# NinjaPool-1J-171004.net
KiCad netlist of a schematic drawn in EAGLE
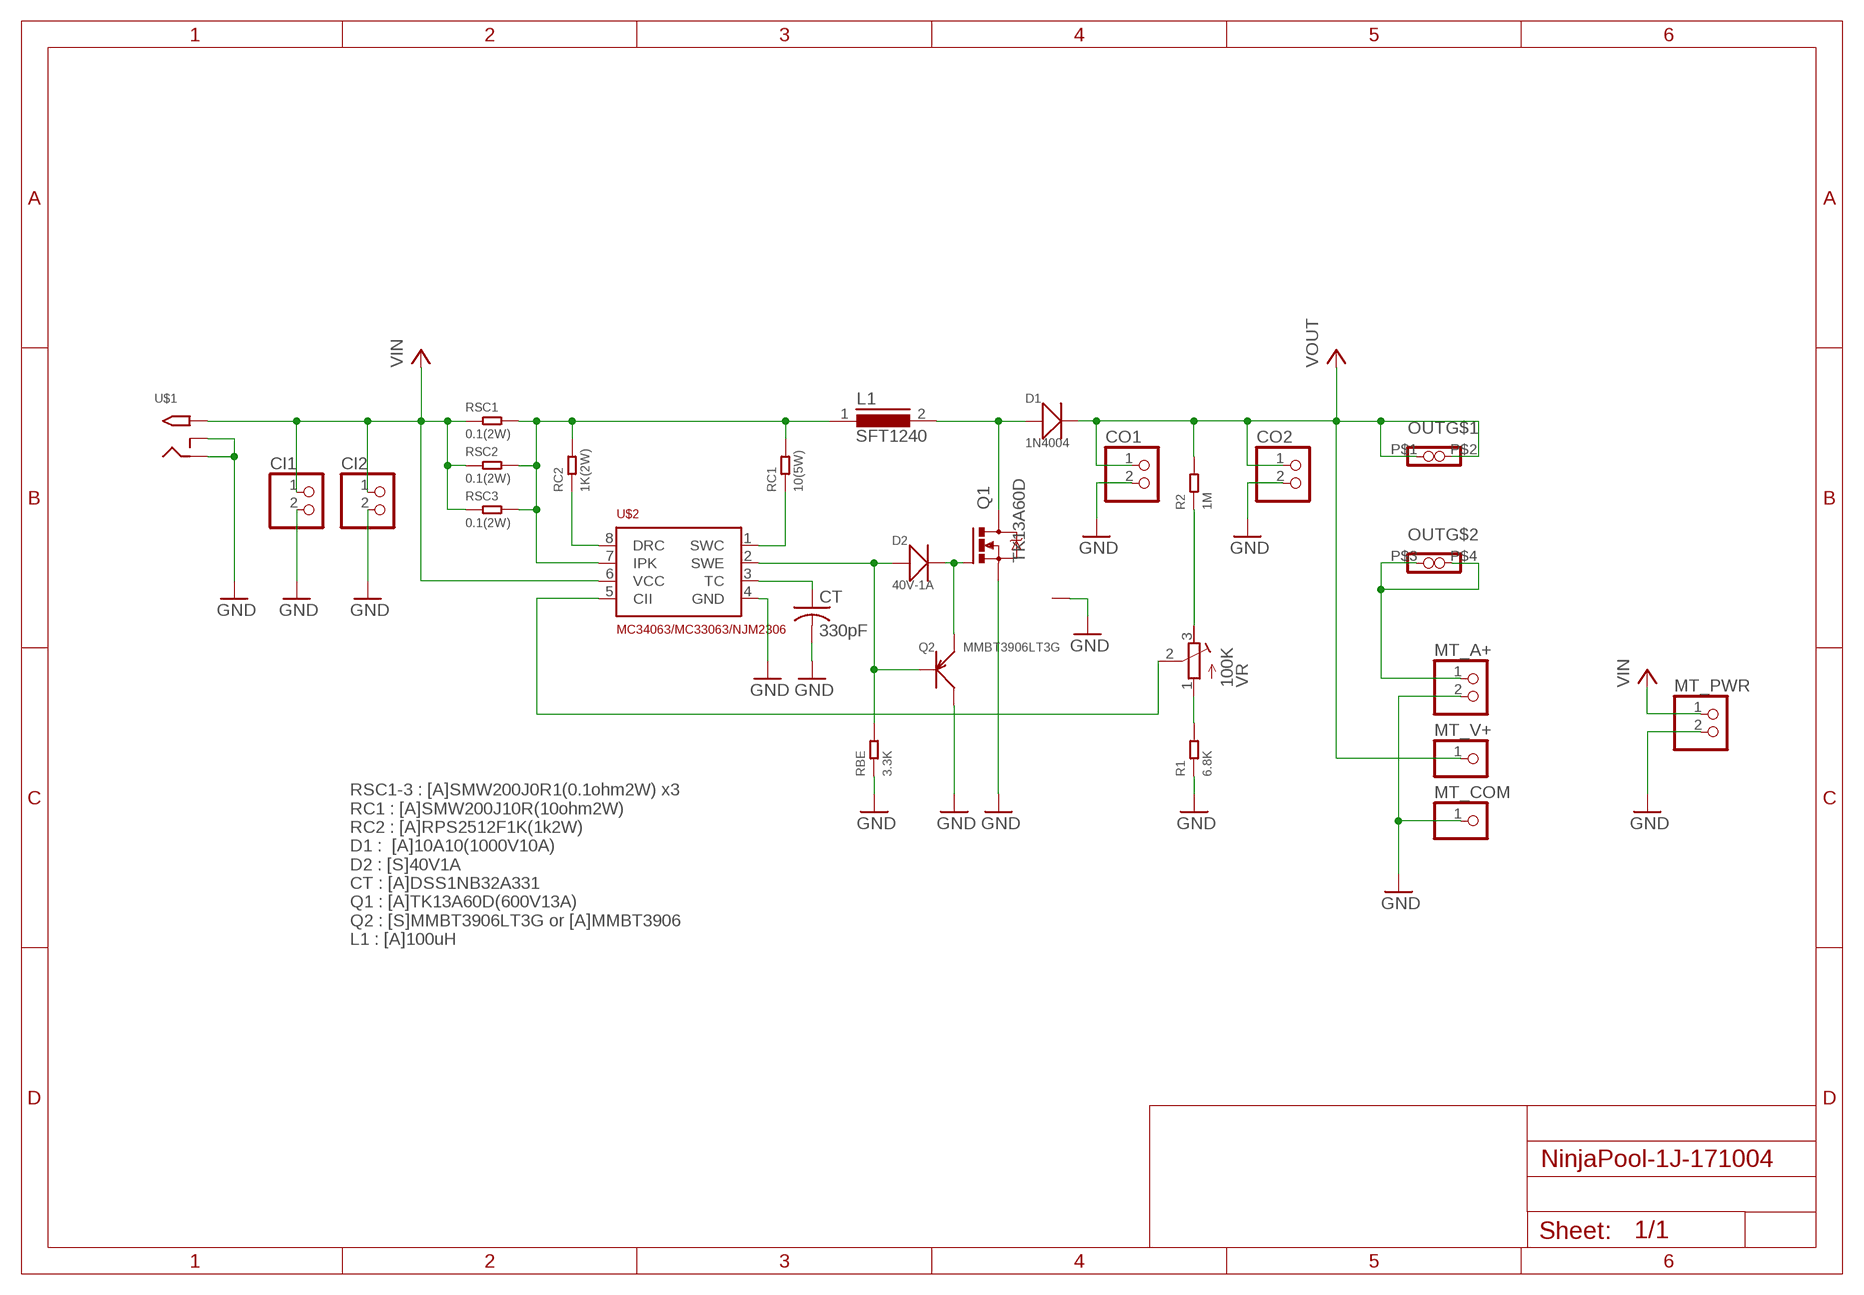
[diagram p0: schematic, sheet 1]

(export (version "E")
  (design (tool "Eeschema 10.0.6"))
  (components
    (comp (ref "CI1")
      (value "PINHD-1X2")
      (footprint "eagle-import:1X02")
      (libsource (lib "eagle-import") (part "PINHD-1X2"))
    )
    (comp (ref "CI2")
      (value "PINHD-1X2")
      (footprint "eagle-import:1X02")
      (libsource (lib "eagle-import") (part "PINHD-1X2"))
    )
    (comp (ref "CO1")
      (value "PINHD-1X2")
      (footprint "eagle-import:1X02")
      (libsource (lib "eagle-import") (part "PINHD-1X2"))
    )
    (comp (ref "CO2")
      (value "PINHD-1X2")
      (footprint "eagle-import:1X02")
      (libsource (lib "eagle-import") (part "PINHD-1X2"))
    )
    (comp (ref "CT")
      (value "330pF")
      (footprint "eagle-import:C050-024X044")
      (libsource (lib "eagle-import") (part "C-US050-024X044"))
    )
    (comp (ref "D1")
      (value "1N4004")
      (footprint "eagle-import:DO-41")
      (libsource (lib "eagle-import") (part "DIP-DIODE-400V-1A(DO-41)"))
    )
    (comp (ref "D2")
      (value "40V-1A")
      (footprint "eagle-import:DO-214AC")
      (fields (field (name "MPN") "1N5819"))
      (libsource (lib "eagle-import") (part "SMD-DIODE-SCHOTTKY-40V-1A(DO-214AC)"))
    )
    (comp (ref "HEAT")
      (value "HEAT111PB015")
      (footprint "eagle-import:HEAT11PB015")
      (libsource (lib "eagle-import") (part "HEAT111PB015"))
    )
    (comp (ref "L1")
      (value "SFT1240")
      (footprint "eagle-import:SFT1240")
      (libsource (lib "eagle-import") (part "SFT1240"))
    )
    (comp (ref "MT_A+")
      (value "PINHD-1X2")
      (footprint "eagle-import:1X02")
      (libsource (lib "eagle-import") (part "PINHD-1X2"))
    )
    (comp (ref "MT_COM")
      (value "PINHD-1X1")
      (footprint "eagle-import:1X01")
      (libsource (lib "eagle-import") (part "PINHD-1X1"))
    )
    (comp (ref "MT_PWR")
      (value "PINHD-1X2")
      (footprint "eagle-import:1X02")
      (libsource (lib "eagle-import") (part "PINHD-1X2"))
    )
    (comp (ref "MT_V+")
      (value "PINHD-1X1")
      (footprint "eagle-import:1X01")
      (libsource (lib "eagle-import") (part "PINHD-1X1"))
    )
    (comp (ref "OUT")
      (value "BANANA")
      (footprint "eagle-import:BANANA_TMP")
      (libsource (lib "eagle-import") (part "BANANA"))
    )
    (comp (ref "Q1")
      (value "TK13A60D")
      (footprint "eagle-import:TO220BV")
      (libsource (lib "eagle-import") (part "IRF520"))
    )
    (comp (ref "Q2")
      (value "MMBT3906LT3G")
      (footprint "eagle-import:SOT-23")
      (libsource (lib "eagle-import") (part "SMD-TRANSISTORS-PNP-40V-200MA-MMBT3906LT3G(SOT-23)"))
    )
    (comp (ref "R1")
      (value "6.8K")
      (footprint "eagle-import:R0603")
      (fields (field (name "MPN") "RC0805JR-07220KL"))
      (libsource (lib "eagle-import") (part "SMD-RES-6.8K-1%-1/10W(0603)"))
    )
    (comp (ref "R2")
      (value "1M")
      (footprint "eagle-import:R0603")
      (fields (field (name "MPN") "RC0603FR-071ML"))
      (libsource (lib "eagle-import") (part "SMD-RES-1M-1%-1/10W(0603)"))
    )
    (comp (ref "RBE")
      (value "3.3K")
      (footprint "eagle-import:R0603")
      (libsource (lib "eagle-import") (part "SMD-RES-3.3K-5%-1/10W(0603)"))
    )
    (comp (ref "RC1")
      (value "10(5W)")
      (footprint "eagle-import:SWE500")
      (libsource (lib "eagle-import") (part "SWE500"))
    )
    (comp (ref "RC2")
      (value "1K(2W)")
      (footprint "eagle-import:R2512")
      (libsource (lib "eagle-import") (part "R2512"))
    )
    (comp (ref "RSC1")
      (value "0.1(2W)")
      (footprint "eagle-import:SMW200")
      (libsource (lib "eagle-import") (part "SWE200"))
    )
    (comp (ref "RSC2")
      (value "0.1(2W)")
      (footprint "eagle-import:SMW200")
      (libsource (lib "eagle-import") (part "SWE200"))
    )
    (comp (ref "RSC3")
      (value "0.1(2W)")
      (footprint "eagle-import:SMW200")
      (libsource (lib "eagle-import") (part "SWE200"))
    )
    (comp (ref "U$1")
      (value "2.1MMJACKTHM")
      (footprint "eagle-import:PJ-102A")
      (libsource (lib "eagle-import") (part "2.1MMJACKTHM"))
    )
    (comp (ref "U$2")
      (value "MC34063/MC33063/NJM2306")
      (footprint "eagle-import:DIL8")
      (libsource (lib "eagle-import") (part "MC34063/MC33063/NJM2306"))
    )
    (comp (ref "VR")
      (value "100K")
      (footprint "eagle-import:AITENDO_R16K1")
      (libsource (lib "eagle-import") (part "R-TRIMMAITENDO_R16K1"))
    )
  )
  (nets
    (net (code "1") (name "GND") (class "Default")
      (node (ref "CI1") (pin "2") (pinfunction "2_2") (pintype "passive"))
      (node (ref "CI2") (pin "2") (pinfunction "2_2") (pintype "passive"))
      (node (ref "CO1") (pin "2") (pinfunction "2_2") (pintype "passive"))
      (node (ref "CO2") (pin "2") (pinfunction "2_2") (pintype "passive"))
      (node (ref "CT") (pin "2") (pinfunction "2_2") (pintype "passive"))
      (node (ref "HEAT") (pin "P$1") (pinfunction "P$1_P$1") (pintype "bidirectional"))
      (node (ref "MT_A+") (pin "2") (pinfunction "2_2") (pintype "passive"))
      (node (ref "MT_COM") (pin "1") (pinfunction "1_1") (pintype "passive"))
      (node (ref "MT_PWR") (pin "2") (pinfunction "2_2") (pintype "passive"))
      (node (ref "Q1") (pin "S") (pinfunction "S_S") (pintype "passive"))
      (node (ref "Q2") (pin "3") (pinfunction "C_3") (pintype "passive"))
      (node (ref "R1") (pin "1") (pinfunction "1_1") (pintype "passive"))
      (node (ref "RBE") (pin "1") (pinfunction "1_1") (pintype "passive"))
      (node (ref "U$1") (pin "RING") (pinfunction "RING_RING") (pintype "bidirectional"))
      (node (ref "U$1") (pin "RING_SW") (pinfunction "RING_SW_RING_SW") (pintype "bidirectional"))
      (node (ref "U$2") (pin "4") (pinfunction "GND_4") (pintype "bidirectional"))
    )
    (net (code "2") (name "Net-(D1-+)") (class "Default")
      (node (ref "D1") (pin "1") (pinfunction "+_1") (pintype "passive"))
      (node (ref "L1") (pin "2") (pinfunction "2_2") (pintype "passive"))
      (node (ref "Q1") (pin "D") (pinfunction "D_D") (pintype "passive"))
    )
    (net (code "3") (name "Net-(D2-+)") (class "Default")
      (node (ref "D2") (pin "1") (pinfunction "+_1") (pintype "passive"))
      (node (ref "Q2") (pin "1") (pinfunction "B_1") (pintype "passive"))
      (node (ref "RBE") (pin "2") (pinfunction "2_2") (pintype "passive"))
      (node (ref "U$2") (pin "2") (pinfunction "SWE_2") (pintype "bidirectional"))
    )
    (net (code "4") (name "Net-(D2--)") (class "Default")
      (node (ref "D2") (pin "2") (pinfunction "-_2") (pintype "passive"))
      (node (ref "Q1") (pin "G") (pinfunction "G_G") (pintype "passive"))
      (node (ref "Q2") (pin "2") (pinfunction "E_2") (pintype "passive"))
    )
    (net (code "5") (name "Net-(OUTB-1)") (class "Default")
      (node (ref "MT_A+") (pin "1") (pinfunction "1_1") (pintype "passive"))
      (node (ref "OUT") (pin "P$3") (pinfunction "1_P$3") (pintype "passive"))
      (node (ref "OUT") (pin "P$4") (pinfunction "2_P$4") (pintype "passive"))
    )
    (net (code "6") (name "Net-(U$2-CII)") (class "Default")
      (node (ref "U$2") (pin "5") (pinfunction "CII_5") (pintype "bidirectional"))
      (node (ref "VR") (pin "2") (pinfunction "S_2") (pintype "passive"))
    )
    (net (code "7") (name "Net-(U$2-DRC)") (class "Default")
      (node (ref "RC2") (pin "1") (pinfunction "1_1") (pintype "passive"))
      (node (ref "U$2") (pin "8") (pinfunction "DRC_8") (pintype "bidirectional"))
    )
    (net (code "8") (name "Net-(U$2-IPK)") (class "Default")
      (node (ref "L1") (pin "1") (pinfunction "1_1") (pintype "passive"))
      (node (ref "RC1") (pin "2") (pinfunction "2_2") (pintype "passive"))
      (node (ref "RC2") (pin "2") (pinfunction "2_2") (pintype "passive"))
      (node (ref "RSC1") (pin "2") (pinfunction "2_2") (pintype "passive"))
      (node (ref "RSC2") (pin "2") (pinfunction "2_2") (pintype "passive"))
      (node (ref "RSC3") (pin "2") (pinfunction "2_2") (pintype "passive"))
      (node (ref "U$2") (pin "7") (pinfunction "IPK_7") (pintype "bidirectional"))
    )
    (net (code "9") (name "Net-(U$2-SWC)") (class "Default")
      (node (ref "RC1") (pin "1") (pinfunction "1_1") (pintype "passive"))
      (node (ref "U$2") (pin "1") (pinfunction "SWC_1") (pintype "bidirectional"))
    )
    (net (code "10") (name "Net-(U$2-TC)") (class "Default")
      (node (ref "CT") (pin "1") (pinfunction "1_1") (pintype "passive"))
      (node (ref "U$2") (pin "3") (pinfunction "TC_3") (pintype "bidirectional"))
    )
    (net (code "11") (name "Net-(VR-A)") (class "Default")
      (node (ref "R1") (pin "2") (pinfunction "2_2") (pintype "passive"))
      (node (ref "VR") (pin "1") (pinfunction "A_1") (pintype "passive"))
    )
    (net (code "12") (name "Net-(VR-E)") (class "Default")
      (node (ref "R2") (pin "1") (pinfunction "1_1") (pintype "passive"))
      (node (ref "VR") (pin "3") (pinfunction "E_3") (pintype "passive"))
    )
    (net (code "13") (name "VIN") (class "Default")
      (node (ref "CI1") (pin "1") (pinfunction "1_1") (pintype "passive"))
      (node (ref "CI2") (pin "1") (pinfunction "1_1") (pintype "passive"))
      (node (ref "MT_PWR") (pin "1") (pinfunction "1_1") (pintype "passive"))
      (node (ref "RSC1") (pin "1") (pinfunction "1_1") (pintype "passive"))
      (node (ref "RSC2") (pin "1") (pinfunction "1_1") (pintype "passive"))
      (node (ref "RSC3") (pin "1") (pinfunction "1_1") (pintype "passive"))
      (node (ref "U$1") (pin "TIP") (pinfunction "TIP_TIP") (pintype "bidirectional"))
      (node (ref "U$2") (pin "6") (pinfunction "VCC_6") (pintype "bidirectional"))
    )
    (net (code "14") (name "VOUT") (class "Default")
      (node (ref "CO1") (pin "1") (pinfunction "1_1") (pintype "passive"))
      (node (ref "CO2") (pin "1") (pinfunction "1_1") (pintype "passive"))
      (node (ref "D1") (pin "2") (pinfunction "-_2") (pintype "passive"))
      (node (ref "MT_V+") (pin "1") (pinfunction "1_1") (pintype "passive"))
      (node (ref "OUT") (pin "P$1") (pinfunction "1_P$1") (pintype "passive"))
      (node (ref "OUT") (pin "P$2") (pinfunction "2_P$2") (pintype "passive"))
      (node (ref "R2") (pin "2") (pinfunction "2_2") (pintype "passive"))
    )
  )
)
